# micro.net
KiCad netlist of a schematic drawn in Altium Designer
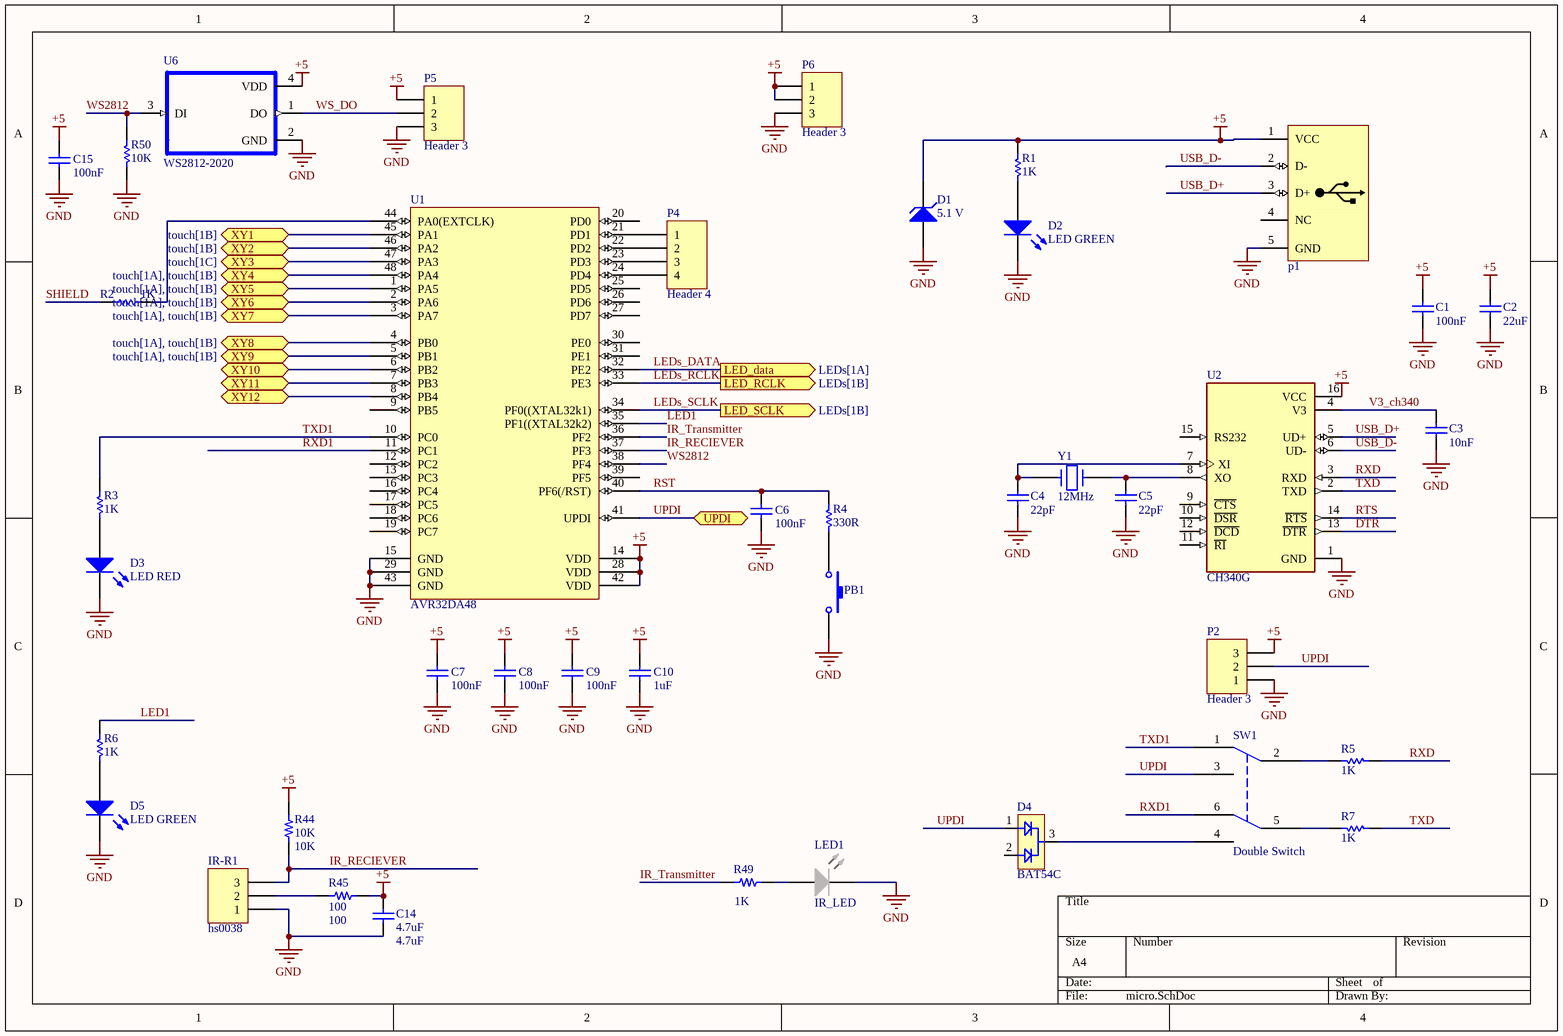
[diagram p0: micro.SchDoc]

(export (version "E")
  (design (tool "Eeschema 10.0.6"))
  (components
    (comp (ref "C1")
      (value "100nF")
      (footprint "SMD_CAP_0805")
      (description "CAP SMD 0805")
      (fields (field (name "PUBLISHER") "Altium Limited"))
      (libsource (lib "Miscellaneous Devices") (part "Cap"))
    )
    (comp (ref "C2")
      (value "22uF")
      (footprint "SMD_CAP_0805")
      (description "CAP SMD 0805")
      (fields (field (name "PUBLISHER") "Altium Limited"))
      (libsource (lib "Miscellaneous Devices") (part "Cap"))
    )
    (comp (ref "C3")
      (value "10nF")
      (footprint "SMD_CAP_0805")
      (description "CAP SMD 0805")
      (fields (field (name "PUBLISHER") "Altium Limited"))
      (libsource (lib "Miscellaneous Devices") (part "Cap"))
    )
    (comp (ref "C4")
      (value "22pF")
      (footprint "SMD_CAP_0805")
      (description "CAP SMD 0805")
      (fields (field (name "PUBLISHER") "Altium Limited"))
      (libsource (lib "Miscellaneous Devices") (part "Cap"))
    )
    (comp (ref "C5")
      (value "22pF")
      (footprint "SMD_CAP_0805")
      (description "CAP SMD 0805")
      (fields (field (name "PUBLISHER") "Altium Limited"))
      (libsource (lib "Miscellaneous Devices") (part "Cap"))
    )
    (comp (ref "C6")
      (value "100nF")
      (footprint "CAP0805")
      (description "CAP seramic")
      (fields (field (name "Comment") "cap 100nF"))
      (libsource (lib "Altium library (www.AVRelec.com)") (part "Cap ceramic"))
    )
    (comp (ref "C7")
      (value "100nF")
      (footprint "CAP0805")
      (description "CAP seramic")
      (fields (field (name "Comment") "cap 100nF"))
      (libsource (lib "Altium library (www.AVRelec.com)") (part "Cap ceramic"))
    )
    (comp (ref "C8")
      (value "100nF")
      (footprint "CAP0805")
      (description "CAP seramic")
      (fields (field (name "Comment") "cap 100nF"))
      (libsource (lib "Altium library (www.AVRelec.com)") (part "Cap ceramic"))
    )
    (comp (ref "C9")
      (value "100nF")
      (footprint "CAP0805")
      (description "CAP seramic")
      (fields (field (name "Comment") "cap 100nF"))
      (libsource (lib "Altium library (www.AVRelec.com)") (part "Cap ceramic"))
    )
    (comp (ref "C10")
      (value "1uF")
      (footprint "CAP0805")
      (description "CAP seramic")
      (fields (field (name "Comment") "cap 1uF"))
      (libsource (lib "Altium library (www.AVRelec.com)") (part "Cap ceramic"))
    )
    (comp (ref "C14")
      (value "4.7uF")
      (footprint "CAP0805")
      (description "CAP SMD 0603")
      (fields (field (name "ALTIUM_VALUE") "4.7uF") (field (name "PUBLISHER") "Altium Limited"))
      (libsource (lib "Miscellaneous Devices") (part "Cap"))
    )
    (comp (ref "C15")
      (value "100nF")
      (footprint "CAP0805")
      (description "CAP seramic")
      (fields (field (name "Comment") "cap 100nF"))
      (libsource (lib "Altium library (www.AVRelec.com)") (part "Cap ceramic"))
    )
    (comp (ref "D1")
      (value "Diode Zener")
      (footprint "Diode 1n4148 SMD")
      (description "Zener Diode")
      (fields (field (name "VOLTAGE") "5.1 V") (field (name "DESIGNER") "Saeid Jorablo"))
      (libsource (lib "Altium") (part "Diode Zener"))
    )
    (comp (ref "D2")
      (value "LED GREEN")
      (footprint "LED_0805 G")
      (description "LED SMD 0805 GREEN")
      (fields (field (name "PUBLISHER") "Altium Limited"))
      (libsource (lib "Miscellaneous Devices") (part "LED0"))
    )
    (comp (ref "D3")
      (value "LED RED")
      (footprint "LED_0805 G")
      (description "LED SMD 0805 RED")
      (fields (field (name "PUBLISHER") "Altium Limited"))
      (libsource (lib "Miscellaneous Devices") (part "LED0"))
    )
    (comp (ref "D4") (value "BAT54C") (footprint "SOT-23") (libsource (lib "ZetaBoard_Lib") (part "BAT54C")))
    (comp (ref "D5")
      (value "LED GREEN")
      (footprint "LED_0805 G")
      (description "LED SMD 0805 GREEN")
      (fields (field (name "PUBLISHER") "Altium Limited"))
      (libsource (lib "Miscellaneous Devices") (part "LED0"))
    )
    (comp (ref "IR-R1")
      (value "hs0038")
      (footprint "HS3800B")
      (description "Header, 3-Pin, Right Angle")
      (fields (field (name "PUBLISHER") "Altium Limited"))
      (libsource (lib "Miscellaneous Connectors") (part "Header 3H"))
    )
    (comp (ref "LED1") (value "IR_LED") (footprint "LED_WHITE") (libsource (lib "LED5") (part "LED-W")))
    (comp (ref "p1")
      (value "USB Connector")
      (footprint "USB_AB_BM_SHS")
      (description "USB Connector MICRO-B Type")
      (fields (field (name "DESIGNER") "ABBAS BASEREH") (field (name "PUBLISHER") "ABBAS BASEREH"))
      (libsource (lib "Altium (2)") (part "USB MICRO"))
    )
    (comp (ref "P2")
      (value "Header 3")
      (footprint "HDR1X3")
      (description "Header, 3-Pin")
      (fields (field (name "PUBLISHER") "Altium Limited"))
      (libsource (lib "") (part "Header 3_1"))
    )
    (comp (ref "P4")
      (value "Header 4")
      (footprint "HDR1X4")
      (description "Header, 4-Pin")
      (fields (field (name "PUBLISHER") "Altium Limited"))
      (libsource (lib "Miscellaneous Connectors") (part "Header 4"))
    )
    (comp (ref "P5")
      (value "Header 3")
      (footprint "HDR1X3")
      (description "Header, 3-Pin")
      (fields (field (name "PUBLISHER") "Altium Limited"))
      (libsource (lib "Miscellaneous Connectors") (part "Header 3"))
    )
    (comp (ref "P6")
      (value "Header 3")
      (footprint "HDR1X3")
      (description "Header, 3-Pin")
      (fields (field (name "PUBLISHER") "Altium Limited"))
      (libsource (lib "Miscellaneous Connectors") (part "Header 3"))
    )
    (comp (ref "PB1")
      (value "Push-Button-tall")
      (footprint "tack-sw-3x5x6")
      (libsource (lib "Mine-Discreet") (part "Push-Button-tall"))
    )
    (comp (ref "R1")
      (value "1K")
      (footprint "RES0805")
      (description "Resistor")
      (fields (field (name "Comment") "Res 1K") (field (name "PUBLISHER") "Altium Limited"))
      (libsource (lib "Miscellaneous Devices") (part "Res1"))
    )
    (comp (ref "R2")
      (value "1K")
      (footprint "RES 0805 (2012X06L)")
      (description "Resistor")
      (fields (field (name "PUBLISHER") "Altium Limited"))
      (libsource (lib "Miscellaneous Devices") (part "Res1"))
    )
    (comp (ref "R3")
      (value "1K")
      (footprint "RES0805")
      (description "Resistor")
      (fields (field (name "Comment") "Res 1K") (field (name "PUBLISHER") "Altium Limited"))
      (libsource (lib "Miscellaneous Devices") (part "Res1"))
    )
    (comp (ref "R4")
      (value "330R")
      (footprint "RES0805")
      (description "Resistor")
      (fields (field (name "Comment") "Res 330R") (field (name "PUBLISHER") "Altium Limited"))
      (libsource (lib "Miscellaneous Devices") (part "Res1"))
    )
    (comp (ref "R5")
      (value "1K")
      (footprint "RES0805")
      (description "Resistor")
      (fields (field (name "Comment") "Res 1K") (field (name "PUBLISHER") "Altium Limited"))
      (libsource (lib "Miscellaneous Devices") (part "Res1"))
    )
    (comp (ref "R6")
      (value "1K")
      (footprint "RES0805")
      (description "Resistor")
      (fields (field (name "Comment") "Res 1K") (field (name "PUBLISHER") "Altium Limited"))
      (libsource (lib "Miscellaneous Devices") (part "Res1"))
    )
    (comp (ref "R7")
      (value "1K")
      (footprint "RES0805")
      (description "Resistor")
      (fields (field (name "Comment") "Res 1K") (field (name "PUBLISHER") "Altium Limited"))
      (libsource (lib "Miscellaneous Devices") (part "Res1"))
    )
    (comp (ref "R44")
      (value "10K")
      (footprint "RES0805")
      (description "RES SMD 0603")
      (fields (field (name "PART NUMBER") "RCS0805100KFKEA") (field (name "ALTIUM_VALUE") "10K"))
      (libsource (lib "lamp control-ver2") (part "Resistor"))
    )
    (comp (ref "R45")
      (value "100")
      (footprint "RES0805")
      (description "RES SMD 0603")
      (fields (field (name "PART NUMBER") "RCS0805100KFKEA") (field (name "ALTIUM_VALUE") "100"))
      (libsource (lib "lamp control-ver2") (part "Resistor"))
    )
    (comp (ref "R49")
      (value "1K")
      (footprint "RES0805")
      (description "RES SMD 0603")
      (fields (field (name "PART NUMBER") "RCS0805100KFKEA"))
      (libsource (lib "lamp control-ver2") (part "Resistor"))
    )
    (comp (ref "R50")
      (value "10K")
      (footprint "RES0805")
      (description "Resistor")
      (fields (field (name "Comment") "Res 10K") (field (name "PUBLISHER") "Altium Limited"))
      (libsource (lib "Miscellaneous Devices") (part "Res1"))
    )
    (comp (ref "SW1")
      (value "Double Switch")
      (footprint "switch_2way_DPDT_right")
      (description "DPDT Switch")
      (libsource (lib "My Library") (part "Switch - DPDT"))
    )
    (comp (ref "U1")
      (value "AVR32DA48")
      (footprint "TQPF48")
      (libsource (lib "AVR_DA_family") (part "AVR32DA48"))
    )
    (comp (ref "U2")
      (value "CH340G")
      (footprint "SOIC16_N")
      (description "USB Interface Integrated Circuit")
      (fields (field (name "MP") "Ch340G") (field (name "MF") "WCH"))
      (libsource (lib "ESP32") (part "CH340G"))
    )
    (comp (ref "U6")
      (value "WS2812-2020")
      (footprint "LED_WS2812B-5050")
      (description "Intelligent control LED integrated light source")
      (fields (field (name "MF") "Worldsemi"))
      (libsource (lib "ESP32") (part "WS2812-2020"))
    )
    (comp (ref "Y1")
      (value "12MHz")
      (footprint "XTAL_SMD")
      (description "Crystal")
      (libsource (lib "Altium library (www.AVRelec.com)") (part "CRYSTAL"))
    )
  )
  (nets
    (net (code "1") (name "+5") (class "Default")
      (node (ref "C1") (pin "2") (pinfunction "2_2") (pintype "passive"))
      (node (ref "C10") (pin "2") (pinfunction "2_2") (pintype "passive"))
      (node (ref "C14") (pin "2") (pinfunction "2_2") (pintype "passive"))
      (node (ref "C15") (pin "2") (pinfunction "2_2") (pintype "passive"))
      (node (ref "C2") (pin "2") (pinfunction "2_2") (pintype "passive"))
      (node (ref "C7") (pin "2") (pinfunction "2_2") (pintype "passive"))
      (node (ref "C8") (pin "2") (pinfunction "2_2") (pintype "passive"))
      (node (ref "C9") (pin "2") (pinfunction "2_2") (pintype "passive"))
      (node (ref "D1") (pin "2") (pinfunction "K_2") (pintype "passive"))
      (node (ref "P2") (pin "3") (pinfunction "3_3") (pintype "passive"))
      (node (ref "P5") (pin "1") (pinfunction "1_1") (pintype "passive"))
      (node (ref "P6") (pin "1") (pinfunction "1_1") (pintype "passive"))
      (node (ref "P6") (pin "2") (pinfunction "2_2") (pintype "passive"))
      (node (ref "R1") (pin "1") (pinfunction "1_1") (pintype "passive"))
      (node (ref "R44") (pin "1") (pinfunction "1_1") (pintype "passive"))
      (node (ref "R45") (pin "1") (pinfunction "1_1") (pintype "passive"))
      (node (ref "U1") (pin "14") (pinfunction "VDD_14") (pintype "power_in"))
      (node (ref "U1") (pin "28") (pinfunction "VDD_28") (pintype "power_in"))
      (node (ref "U1") (pin "42") (pinfunction "VDD_42") (pintype "power_in"))
      (node (ref "U2") (pin "16") (pinfunction "VCC_16") (pintype "power_in"))
      (node (ref "U6") (pin "4") (pinfunction "VDD_4") (pintype "power_in"))
      (node (ref "p1") (pin "1") (pinfunction "VCC_1") (pintype "power_in"))
    )
    (net (code "2") (name "/DTR") (class "Default")
      (node (ref "U2") (pin "13") (pinfunction "~{DTR}_13") (pintype "output"))
    )
    (net (code "3") (name "/IR_RECIEVER") (class "Default")
      (node (ref "IR-R1") (pin "3") (pinfunction "3_3") (pintype "passive"))
      (node (ref "R44") (pin "2") (pinfunction "2_2") (pintype "passive"))
      (node (ref "U1") (pin "37") (pinfunction "PF3_37") (pintype "bidirectional"))
    )
    (net (code "4") (name "/IR_Transmitter") (class "Default")
      (node (ref "R49") (pin "2") (pinfunction "2_2") (pintype "passive"))
      (node (ref "U1") (pin "36") (pinfunction "PF2_36") (pintype "bidirectional"))
    )
    (net (code "5") (name "/LED1") (class "Default")
      (node (ref "R6") (pin "1") (pinfunction "1_1") (pintype "passive"))
      (node (ref "U1") (pin "35") (pinfunction "PF1((XTAL32k2)_35") (pintype "bidirectional"))
    )
    (net (code "6") (name "/LEDs_DATA") (class "Default")
      (node (ref "U1") (pin "32") (pinfunction "PE2_32") (pintype "bidirectional"))
    )
    (net (code "7") (name "/LEDs_RCLK") (class "Default")
      (node (ref "U1") (pin "33") (pinfunction "PE3_33") (pintype "bidirectional"))
    )
    (net (code "8") (name "/LEDs_SCLK") (class "Default")
      (node (ref "U1") (pin "34") (pinfunction "PF0((XTAL32k1)_34") (pintype "bidirectional"))
    )
    (net (code "9") (name "/RST") (class "Default")
      (node (ref "C6") (pin "2") (pinfunction "2_2") (pintype "passive"))
      (node (ref "R4") (pin "1") (pinfunction "1_1") (pintype "passive"))
      (node (ref "U1") (pin "40") (pinfunction "PF6(/RST)_40") (pintype "bidirectional"))
    )
    (net (code "10") (name "/RTS") (class "Default")
      (node (ref "U2") (pin "14") (pinfunction "~{RTS}_14") (pintype "output"))
    )
    (net (code "11") (name "/RXD") (class "Default")
      (node (ref "R5") (pin "2") (pinfunction "2_2") (pintype "passive"))
      (node (ref "U2") (pin "3") (pinfunction "RXD_3") (pintype "input"))
    )
    (net (code "12") (name "/RXD1") (class "Default")
      (node (ref "SW1") (pin "6") (pinfunction "6_6") (pintype "passive"))
      (node (ref "U1") (pin "11") (pinfunction "PC1_11") (pintype "bidirectional"))
    )
    (net (code "13") (name "/SHIELD") (class "Default")
      (node (ref "R2") (pin "2") (pinfunction "2_2") (pintype "passive"))
    )
    (net (code "14") (name "/TXD") (class "Default")
      (node (ref "R7") (pin "2") (pinfunction "2_2") (pintype "passive"))
      (node (ref "U2") (pin "2") (pinfunction "TXD_2") (pintype "output"))
    )
    (net (code "15") (name "/TXD1") (class "Default")
      (node (ref "R3") (pin "1") (pinfunction "1_1") (pintype "passive"))
      (node (ref "SW1") (pin "1") (pinfunction "1_1") (pintype "passive"))
      (node (ref "U1") (pin "10") (pinfunction "PC0_10") (pintype "bidirectional"))
    )
    (net (code "16") (name "/UPDI") (class "Default")
      (node (ref "D4") (pin "1") (pintype "passive"))
      (node (ref "P2") (pin "2") (pinfunction "2_2") (pintype "passive"))
      (node (ref "SW1") (pin "3") (pinfunction "3_3") (pintype "passive"))
      (node (ref "U1") (pin "41") (pinfunction "UPDI_41") (pintype "bidirectional"))
    )
    (net (code "17") (name "/USB_D+") (class "Default")
      (node (ref "U2") (pin "5") (pinfunction "UD+_5") (pintype "bidirectional"))
      (node (ref "p1") (pin "3") (pinfunction "D+_3") (pintype "bidirectional"))
    )
    (net (code "18") (name "/USB_D-") (class "Default")
      (node (ref "U2") (pin "6") (pinfunction "UD-_6") (pintype "bidirectional"))
      (node (ref "p1") (pin "2") (pinfunction "D-_2") (pintype "bidirectional"))
    )
    (net (code "19") (name "/V3_ch340") (class "Default")
      (node (ref "C3") (pin "2") (pinfunction "2_2") (pintype "passive"))
      (node (ref "U2") (pin "4") (pinfunction "V3_4") (pintype "power_in"))
    )
    (net (code "20") (name "/WS2812") (class "Default")
      (node (ref "R50") (pin "1") (pinfunction "1_1") (pintype "passive"))
      (node (ref "U1") (pin "38") (pinfunction "PF4_38") (pintype "bidirectional"))
      (node (ref "U6") (pin "3") (pinfunction "DI_3") (pintype "input"))
    )
    (net (code "21") (name "/WS_DO") (class "Default")
      (node (ref "P5") (pin "2") (pinfunction "2_2") (pintype "passive"))
      (node (ref "U6") (pin "1") (pinfunction "DO_1") (pintype "output"))
    )
    (net (code "22") (name "/XY1") (class "Default")
      (node (ref "U1") (pin "45") (pinfunction "PA1_45") (pintype "bidirectional"))
    )
    (net (code "23") (name "/XY2") (class "Default")
      (node (ref "U1") (pin "46") (pinfunction "PA2_46") (pintype "bidirectional"))
    )
    (net (code "24") (name "/XY3") (class "Default")
      (node (ref "U1") (pin "47") (pinfunction "PA3_47") (pintype "bidirectional"))
    )
    (net (code "25") (name "/XY4") (class "Default")
      (node (ref "U1") (pin "48") (pinfunction "PA4_48") (pintype "bidirectional"))
    )
    (net (code "26") (name "/XY5") (class "Default")
      (node (ref "U1") (pin "1") (pinfunction "PA5_1") (pintype "bidirectional"))
    )
    (net (code "27") (name "/XY6") (class "Default")
      (node (ref "U1") (pin "2") (pinfunction "PA6_2") (pintype "bidirectional"))
    )
    (net (code "28") (name "/XY7") (class "Default")
      (node (ref "U1") (pin "3") (pinfunction "PA7_3") (pintype "bidirectional"))
    )
    (net (code "29") (name "/XY8") (class "Default")
      (node (ref "U1") (pin "4") (pinfunction "PB0_4") (pintype "bidirectional"))
    )
    (net (code "30") (name "/XY9") (class "Default")
      (node (ref "U1") (pin "5") (pinfunction "PB1_5") (pintype "bidirectional"))
    )
    (net (code "31") (name "/XY10") (class "Default")
      (node (ref "U1") (pin "6") (pinfunction "PB2_6") (pintype "bidirectional"))
    )
    (net (code "32") (name "/XY11") (class "Default")
      (node (ref "U1") (pin "7") (pinfunction "PB3_7") (pintype "bidirectional"))
    )
    (net (code "33") (name "/XY12") (class "Default")
      (node (ref "U1") (pin "8") (pinfunction "PB4_8") (pintype "bidirectional"))
    )
    (net (code "34") (name "GND") (class "Default")
      (node (ref "C1") (pin "1") (pinfunction "1_1") (pintype "passive"))
      (node (ref "C10") (pin "1") (pinfunction "1_1") (pintype "passive"))
      (node (ref "C14") (pin "1") (pinfunction "1_1") (pintype "passive"))
      (node (ref "C15") (pin "1") (pinfunction "1_1") (pintype "passive"))
      (node (ref "C2") (pin "1") (pinfunction "1_1") (pintype "passive"))
      (node (ref "C3") (pin "1") (pinfunction "1_1") (pintype "passive"))
      (node (ref "C4") (pin "1") (pinfunction "1_1") (pintype "passive"))
      (node (ref "C5") (pin "1") (pinfunction "1_1") (pintype "passive"))
      (node (ref "C6") (pin "1") (pinfunction "1_1") (pintype "passive"))
      (node (ref "C7") (pin "1") (pinfunction "1_1") (pintype "passive"))
      (node (ref "C8") (pin "1") (pinfunction "1_1") (pintype "passive"))
      (node (ref "C9") (pin "1") (pinfunction "1_1") (pintype "passive"))
      (node (ref "D1") (pin "1") (pinfunction "A_1") (pintype "passive"))
      (node (ref "D2") (pin "2") (pinfunction "K_2") (pintype "passive"))
      (node (ref "D3") (pin "2") (pinfunction "K_2") (pintype "passive"))
      (node (ref "D5") (pin "2") (pinfunction "K_2") (pintype "passive"))
      (node (ref "IR-R1") (pin "1") (pinfunction "1_1") (pintype "passive"))
      (node (ref "LED1") (pin "K") (pinfunction "K_K") (pintype "passive"))
      (node (ref "P2") (pin "1") (pinfunction "1_1") (pintype "passive"))
      (node (ref "P5") (pin "3") (pinfunction "3_3") (pintype "passive"))
      (node (ref "P6") (pin "3") (pinfunction "3_3") (pintype "passive"))
      (node (ref "PB1") (pin "1") (pinfunction "1_1") (pintype "passive"))
      (node (ref "R50") (pin "2") (pinfunction "2_2") (pintype "passive"))
      (node (ref "U1") (pin "15") (pinfunction "GND_15") (pintype "power_in"))
      (node (ref "U1") (pin "29") (pinfunction "GND_29") (pintype "power_in"))
      (node (ref "U1") (pin "43") (pinfunction "GND_43") (pintype "power_in"))
      (node (ref "U2") (pin "1") (pinfunction "GND_1") (pintype "power_in"))
      (node (ref "U6") (pin "2") (pinfunction "GND_2") (pintype "power_in"))
      (node (ref "p1") (pin "5") (pinfunction "GND_5") (pintype "power_in"))
    )
    (net (code "35") (name "Net-(D2-A)") (class "Default")
      (node (ref "D2") (pin "1") (pinfunction "A_1") (pintype "passive"))
      (node (ref "R1") (pin "2") (pinfunction "2_2") (pintype "passive"))
    )
    (net (code "36") (name "Net-(D3-A)") (class "Default")
      (node (ref "D3") (pin "1") (pinfunction "A_1") (pintype "passive"))
      (node (ref "R3") (pin "2") (pinfunction "2_2") (pintype "passive"))
    )
    (net (code "37") (name "Net-(D4-Pad3)") (class "Default")
      (node (ref "D4") (pin "3") (pintype "passive"))
      (node (ref "SW1") (pin "4") (pinfunction "4_4") (pintype "passive"))
    )
    (net (code "38") (name "Net-(D5-A)") (class "Default")
      (node (ref "D5") (pin "1") (pinfunction "A_1") (pintype "passive"))
      (node (ref "R6") (pin "2") (pinfunction "2_2") (pintype "passive"))
    )
    (net (code "39") (name "Net-(IR-R1-Pad2)") (class "Default")
      (node (ref "IR-R1") (pin "2") (pinfunction "2_2") (pintype "passive"))
      (node (ref "R45") (pin "2") (pinfunction "2_2") (pintype "passive"))
    )
    (net (code "40") (name "Net-(LED1-PadA)") (class "Default")
      (node (ref "LED1") (pin "A") (pinfunction "A_A") (pintype "passive"))
      (node (ref "R49") (pin "1") (pinfunction "1_1") (pintype "passive"))
    )
    (net (code "41") (name "Net-(PB1-Pad2)") (class "Default")
      (node (ref "PB1") (pin "2") (pinfunction "2_2") (pintype "passive"))
      (node (ref "R4") (pin "2") (pinfunction "2_2") (pintype "passive"))
    )
    (net (code "42") (name "Net-(R5-Pad1)") (class "Default")
      (node (ref "R5") (pin "1") (pinfunction "1_1") (pintype "passive"))
      (node (ref "SW1") (pin "2") (pinfunction "2_2") (pintype "passive"))
    )
    (net (code "43") (name "Net-(R7-Pad1)") (class "Default")
      (node (ref "R7") (pin "1") (pinfunction "1_1") (pintype "passive"))
      (node (ref "SW1") (pin "5") (pinfunction "5_5") (pintype "passive"))
    )
    (net (code "44") (name "Net-(U1-PA0(EXTCLK))") (class "Default")
      (node (ref "R2") (pin "1") (pinfunction "1_1") (pintype "passive"))
      (node (ref "U1") (pin "44") (pinfunction "PA0(EXTCLK)_44") (pintype "bidirectional"))
    )
    (net (code "45") (name "Net-(U1-PD1)") (class "Default")
      (node (ref "P4") (pin "1") (pinfunction "1_1") (pintype "passive"))
      (node (ref "U1") (pin "21") (pinfunction "PD1_21") (pintype "bidirectional"))
    )
    (net (code "46") (name "Net-(U1-PD2)") (class "Default")
      (node (ref "P4") (pin "2") (pinfunction "2_2") (pintype "passive"))
      (node (ref "U1") (pin "22") (pinfunction "PD2_22") (pintype "bidirectional"))
    )
    (net (code "47") (name "Net-(U1-PD3)") (class "Default")
      (node (ref "P4") (pin "3") (pinfunction "3_3") (pintype "passive"))
      (node (ref "U1") (pin "23") (pinfunction "PD3_23") (pintype "bidirectional"))
    )
    (net (code "48") (name "Net-(U1-PD4)") (class "Default")
      (node (ref "P4") (pin "4") (pinfunction "4_4") (pintype "passive"))
      (node (ref "U1") (pin "24") (pinfunction "PD4_24") (pintype "bidirectional"))
    )
    (net (code "49") (name "Net-(U2-XI)") (class "Default")
      (node (ref "C4") (pin "2") (pinfunction "2_2") (pintype "passive"))
      (node (ref "U2") (pin "7") (pinfunction "XI_7") (pintype "input"))
      (node (ref "Y1") (pin "1") (pinfunction "1_1") (pintype "passive"))
    )
    (net (code "50") (name "Net-(U2-XO)") (class "Default")
      (node (ref "C5") (pin "2") (pinfunction "2_2") (pintype "passive"))
      (node (ref "U2") (pin "8") (pinfunction "XO_8") (pintype "output"))
      (node (ref "Y1") (pin "2") (pinfunction "2_2") (pintype "passive"))
    )
    (net (code "51") (name "unconnected-(D4-Pad2)") (class "Default")
      (node (ref "D4") (pin "2") (pintype "passive"))
    )
    (net (code "52") (name "unconnected-(U1-PB5-Pad9)") (class "Default")
      (node (ref "U1") (pin "9") (pinfunction "PB5_9") (pintype "bidirectional"))
    )
    (net (code "53") (name "unconnected-(U1-PC2-Pad12)") (class "Default")
      (node (ref "U1") (pin "12") (pinfunction "PC2_12") (pintype "bidirectional"))
    )
    (net (code "54") (name "unconnected-(U1-PC3-Pad13)") (class "Default")
      (node (ref "U1") (pin "13") (pinfunction "PC3_13") (pintype "bidirectional"))
    )
    (net (code "55") (name "unconnected-(U1-PC4-Pad16)") (class "Default")
      (node (ref "U1") (pin "16") (pinfunction "PC4_16") (pintype "bidirectional"))
    )
    (net (code "56") (name "unconnected-(U1-PC5-Pad17)") (class "Default")
      (node (ref "U1") (pin "17") (pinfunction "PC5_17") (pintype "bidirectional"))
    )
    (net (code "57") (name "unconnected-(U1-PC6-Pad18)") (class "Default")
      (node (ref "U1") (pin "18") (pinfunction "PC6_18") (pintype "bidirectional"))
    )
    (net (code "58") (name "unconnected-(U1-PC7-Pad19)") (class "Default")
      (node (ref "U1") (pin "19") (pinfunction "PC7_19") (pintype "bidirectional"))
    )
    (net (code "59") (name "unconnected-(U1-PD0-Pad20)") (class "Default")
      (node (ref "U1") (pin "20") (pinfunction "PD0_20") (pintype "bidirectional"))
    )
    (net (code "60") (name "unconnected-(U1-PD5-Pad25)") (class "Default")
      (node (ref "U1") (pin "25") (pinfunction "PD5_25") (pintype "bidirectional"))
    )
    (net (code "61") (name "unconnected-(U1-PD6-Pad26)") (class "Default")
      (node (ref "U1") (pin "26") (pinfunction "PD6_26") (pintype "bidirectional"))
    )
    (net (code "62") (name "unconnected-(U1-PD7-Pad27)") (class "Default")
      (node (ref "U1") (pin "27") (pinfunction "PD7_27") (pintype "bidirectional"))
    )
    (net (code "63") (name "unconnected-(U1-PE0-Pad30)") (class "Default")
      (node (ref "U1") (pin "30") (pinfunction "PE0_30") (pintype "bidirectional"))
    )
    (net (code "64") (name "unconnected-(U1-PE1-Pad31)") (class "Default")
      (node (ref "U1") (pin "31") (pinfunction "PE1_31") (pintype "bidirectional"))
    )
    (net (code "65") (name "unconnected-(U1-PF5-Pad39)") (class "Default")
      (node (ref "U1") (pin "39") (pinfunction "PF5_39") (pintype "bidirectional"))
    )
    (net (code "66") (name "unconnected-(U2-RS232-Pad15)") (class "Default")
      (node (ref "U2") (pin "15") (pinfunction "RS232_15") (pintype "input"))
    )
    (net (code "67") (name "unconnected-(U2-~{CTS}-Pad9)") (class "Default")
      (node (ref "U2") (pin "9") (pinfunction "~{CTS}_9") (pintype "input"))
    )
    (net (code "68") (name "unconnected-(U2-~{DCD}-Pad12)") (class "Default")
      (node (ref "U2") (pin "12") (pinfunction "~{DCD}_12") (pintype "input"))
    )
    (net (code "69") (name "unconnected-(U2-~{DSR}-Pad10)") (class "Default")
      (node (ref "U2") (pin "10") (pinfunction "~{DSR}_10") (pintype "input"))
    )
    (net (code "70") (name "unconnected-(U2-~{RI}-Pad11)") (class "Default")
      (node (ref "U2") (pin "11") (pinfunction "~{RI}_11") (pintype "input"))
    )
    (net (code "71") (name "unconnected-(p1-NC-Pad4)") (class "Default")
      (node (ref "p1") (pin "4") (pinfunction "NC_4") (pintype "passive"))
    )
  )
)
